# Ext_conn.net
KiCad netlist of a schematic drawn in Altium Designer
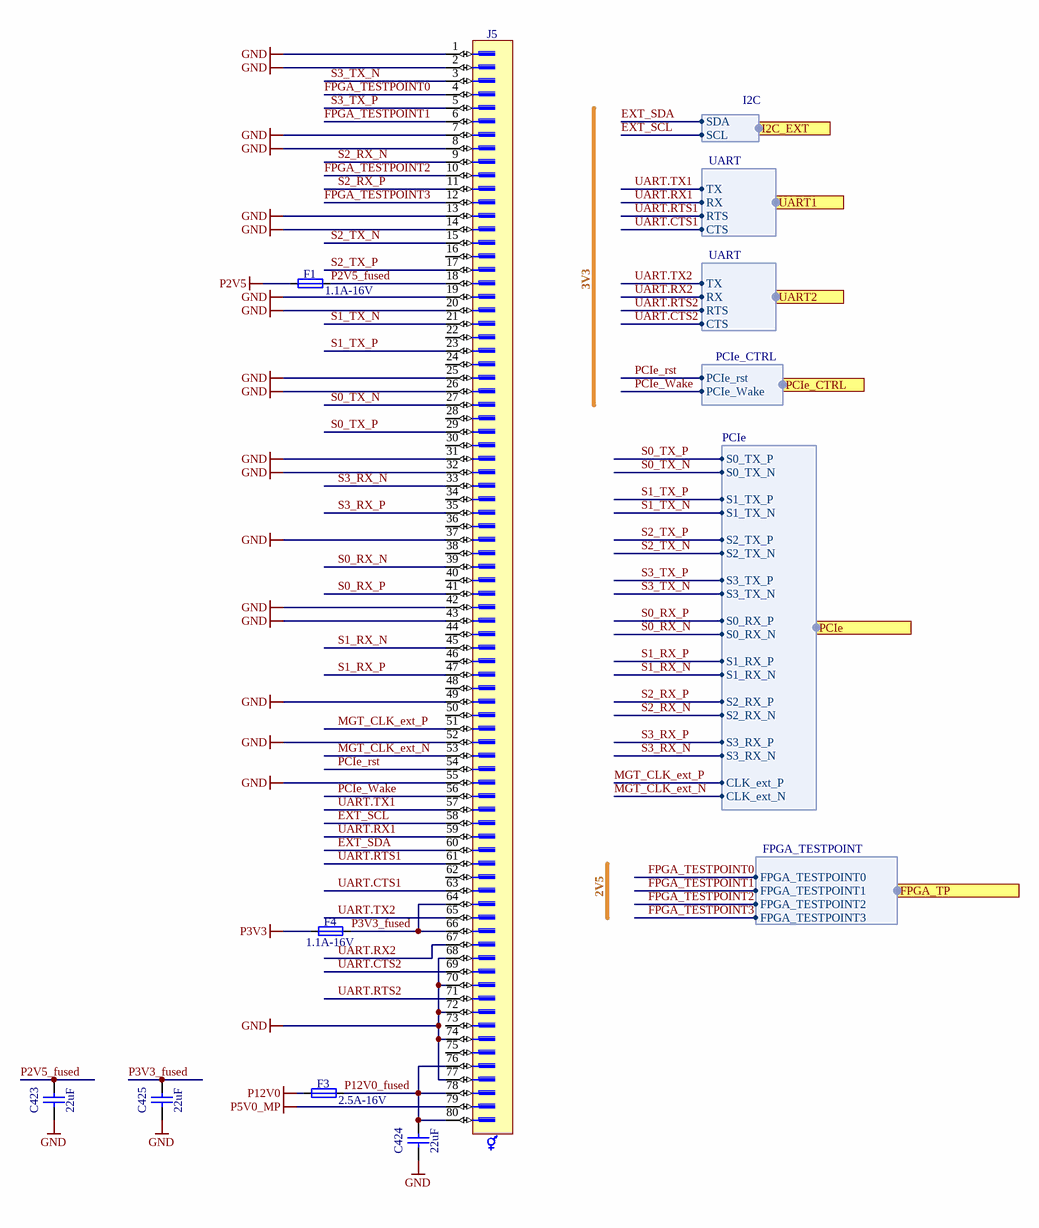
[diagram p0: Ext_conn.schdoc]

(export (version "E")
  (design (tool "Eeschema 10.0.6"))
  (components
    (comp (ref "C423")
      (value "22uF")
      (footprint "CAPC2012X135N")
      (description "Non-polarised capacitor")
      (fields
        (field (name "MANUFACTURER PART NUMBER") "CC0805_22UF_16V_10%_X5R")
        (field (name "MANUFACTURER") "GENERIC")
        (field (name "AUTHOR") "CERN DEM JLC")
      )
      (libsource (lib "Capacitors") (part "Capacitor - non polarized"))
    )
    (comp (ref "C424")
      (value "22uF")
      (footprint "CAPC2012X135N")
      (description "Non-polarised capacitor")
      (fields
        (field (name "MANUFACTURER PART NUMBER") "CC0805_22UF_16V_10%_X5R")
        (field (name "MANUFACTURER") "GENERIC")
        (field (name "AUTHOR") "CERN DEM JLC")
      )
      (libsource (lib "Capacitors") (part "Capacitor - non polarized"))
    )
    (comp (ref "C425")
      (value "22uF")
      (footprint "CAPC2012X135N")
      (description "Non-polarised capacitor")
      (fields
        (field (name "MANUFACTURER PART NUMBER") "CC0805_22UF_16V_10%_X5R")
        (field (name "MANUFACTURER") "GENERIC")
        (field (name "AUTHOR") "CERN DEM JLC")
      )
      (libsource (lib "Capacitors") (part "Capacitor - non polarized"))
    )
    (comp (ref "F1")
      (value "1.1A-16V")
      (footprint "FUSR_BOURNS_MF-MSMF_STYLE1(H85)")
      (description "Fuse")
      (fields
        (field (name "PART NUMBER") "FUSR_BOURNS_MF-MSMF110/16-2")
        (field (name "MANUFACTURER") "BOURNS")
        (field (name "AUTHOR") "CERN DEM JLC")
      )
      (libsource (lib "Eletro-mechanical") (part "Fuse"))
    )
    (comp (ref "F3")
      (value "2.5A-16V")
      (footprint "FUSR_BOURNS_MF-MSMF_STYLE2")
      (description "Fuse")
      (fields
        (field (name "PART NUMBER") "FUSR_BOURNS_MF-MSMF250/16X-2")
        (field (name "MANUFACTURER") "BOURNS")
        (field (name "AUTHOR") "CERN DEM JLC")
      )
      (libsource (lib "Eletro-mechanical") (part "Fuse"))
    )
    (comp (ref "F4")
      (value "1.1A-16V")
      (footprint "FUSR_BOURNS_MF-MSMF_STYLE1(H85)")
      (description "Fuse")
      (fields
        (field (name "PART NUMBER") "FUSR_BOURNS_MF-MSMF110/16-2")
        (field (name "MANUFACTURER") "BOURNS")
        (field (name "AUTHOR") "CERN DEM JLC")
      )
      (libsource (lib "Eletro-mechanical") (part "Fuse"))
    )
    (comp (ref "J5")
      (value "~")
      (footprint "SAMTEC_LSS-140-01-L-DV-A")
      (description "Connector 80 Hermaphroditic")
      (fields
        (field (name "PART NUMBER") "SAMTEC_LSS-140-01-L-DV-A")
        (field (name "MANUFACTURER") "SAMTEC")
        (field (name "AUTHOR") "CERN DEM JMW")
      )
      (libsource (lib "Connectors") (part "Connector 80 Hermaphroditic"))
    )
  )
  (nets
    (net (code "6") (name "/EXT_SCL") (class "Default")
      (node (ref "J5") (pin "58") (pinfunction "58_58") (pintype "bidirectional"))
    )
    (net (code "7") (name "/EXT_SDA") (class "Default")
      (node (ref "J5") (pin "60") (pinfunction "60_60") (pintype "bidirectional"))
    )
    (net (code "8") (name "/FPGA_TESTPOINT0") (class "Default")
      (node (ref "J5") (pin "4") (pinfunction "4_4") (pintype "bidirectional"))
    )
    (net (code "9") (name "/FPGA_TESTPOINT1") (class "Default")
      (node (ref "J5") (pin "6") (pinfunction "6_6") (pintype "bidirectional"))
    )
    (net (code "10") (name "/FPGA_TESTPOINT2") (class "Default")
      (node (ref "J5") (pin "10") (pinfunction "10_10") (pintype "bidirectional"))
    )
    (net (code "11") (name "/FPGA_TESTPOINT3") (class "Default")
      (node (ref "J5") (pin "12") (pinfunction "12_12") (pintype "bidirectional"))
    )
    (net (code "12") (name "/MGT_CLK_ext_N") (class "Default")
      (node (ref "J5") (pin "53") (pinfunction "53_53") (pintype "bidirectional"))
    )
    (net (code "13") (name "/MGT_CLK_ext_P") (class "Default")
      (node (ref "J5") (pin "51") (pinfunction "51_51") (pintype "bidirectional"))
    )
    (net (code "14") (name "/P2V5_fused") (class "Default")
      (node (ref "C423") (pin "2") (pinfunction "2_2") (pintype "passive"))
      (node (ref "F1") (pin "2") (pinfunction "2_2") (pintype "passive"))
      (node (ref "J5") (pin "18") (pinfunction "18_18") (pintype "bidirectional"))
    )
    (net (code "15") (name "/P3V3_fused") (class "Default")
      (node (ref "C425") (pin "2") (pinfunction "2_2") (pintype "passive"))
      (node (ref "F4") (pin "2") (pinfunction "2_2") (pintype "passive"))
      (node (ref "J5") (pin "64") (pinfunction "64_64") (pintype "bidirectional"))
      (node (ref "J5") (pin "66") (pinfunction "66_66") (pintype "bidirectional"))
    )
    (net (code "16") (name "/P12V0_fused") (class "Default")
      (node (ref "C424") (pin "2") (pinfunction "2_2") (pintype "passive"))
      (node (ref "F3") (pin "2") (pinfunction "2_2") (pintype "passive"))
      (node (ref "J5") (pin "76") (pinfunction "76_76") (pintype "bidirectional"))
      (node (ref "J5") (pin "78") (pinfunction "78_78") (pintype "bidirectional"))
      (node (ref "J5") (pin "80") (pinfunction "80_80") (pintype "bidirectional"))
    )
    (net (code "17") (name "/PCIe_Wake") (class "Default")
      (node (ref "J5") (pin "56") (pinfunction "56_56") (pintype "bidirectional"))
    )
    (net (code "18") (name "/PCIe_rst") (class "Default")
      (node (ref "J5") (pin "54") (pinfunction "54_54") (pintype "bidirectional"))
    )
    (net (code "19") (name "/S0_RX_N") (class "Default")
      (node (ref "J5") (pin "39") (pinfunction "39_39") (pintype "bidirectional"))
    )
    (net (code "20") (name "/S0_RX_P") (class "Default")
      (node (ref "J5") (pin "41") (pinfunction "41_41") (pintype "bidirectional"))
    )
    (net (code "21") (name "/S0_TX_N") (class "Default")
      (node (ref "J5") (pin "27") (pinfunction "27_27") (pintype "bidirectional"))
    )
    (net (code "22") (name "/S0_TX_P") (class "Default")
      (node (ref "J5") (pin "29") (pinfunction "29_29") (pintype "bidirectional"))
    )
    (net (code "23") (name "/S1_RX_N") (class "Default")
      (node (ref "J5") (pin "45") (pinfunction "45_45") (pintype "bidirectional"))
    )
    (net (code "24") (name "/S1_RX_P") (class "Default")
      (node (ref "J5") (pin "47") (pinfunction "47_47") (pintype "bidirectional"))
    )
    (net (code "25") (name "/S1_TX_N") (class "Default")
      (node (ref "J5") (pin "21") (pinfunction "21_21") (pintype "bidirectional"))
    )
    (net (code "26") (name "/S1_TX_P") (class "Default")
      (node (ref "J5") (pin "23") (pinfunction "23_23") (pintype "bidirectional"))
    )
    (net (code "27") (name "/S2_RX_N") (class "Default")
      (node (ref "J5") (pin "9") (pinfunction "9_9") (pintype "bidirectional"))
    )
    (net (code "28") (name "/S2_RX_P") (class "Default")
      (node (ref "J5") (pin "11") (pinfunction "11_11") (pintype "bidirectional"))
    )
    (net (code "29") (name "/S2_TX_N") (class "Default")
      (node (ref "J5") (pin "15") (pinfunction "15_15") (pintype "bidirectional"))
    )
    (net (code "30") (name "/S2_TX_P") (class "Default")
      (node (ref "J5") (pin "17") (pinfunction "17_17") (pintype "bidirectional"))
    )
    (net (code "31") (name "/S3_RX_N") (class "Default")
      (node (ref "J5") (pin "33") (pinfunction "33_33") (pintype "bidirectional"))
    )
    (net (code "32") (name "/S3_RX_P") (class "Default")
      (node (ref "J5") (pin "35") (pinfunction "35_35") (pintype "bidirectional"))
    )
    (net (code "33") (name "/S3_TX_N") (class "Default")
      (node (ref "J5") (pin "3") (pinfunction "3_3") (pintype "bidirectional"))
    )
    (net (code "34") (name "/S3_TX_P") (class "Default")
      (node (ref "J5") (pin "5") (pinfunction "5_5") (pintype "bidirectional"))
    )
    (net (code "35") (name "/UART.CTS1") (class "Default")
      (node (ref "J5") (pin "63") (pinfunction "63_63") (pintype "bidirectional"))
    )
    (net (code "36") (name "/UART.CTS2") (class "Default")
      (node (ref "J5") (pin "69") (pinfunction "69_69") (pintype "bidirectional"))
    )
    (net (code "37") (name "/UART.RTS1") (class "Default")
      (node (ref "J5") (pin "61") (pinfunction "61_61") (pintype "bidirectional"))
    )
    (net (code "38") (name "/UART.RTS2") (class "Default")
      (node (ref "J5") (pin "71") (pinfunction "71_71") (pintype "bidirectional"))
    )
    (net (code "39") (name "/UART.RX1") (class "Default")
      (node (ref "J5") (pin "59") (pinfunction "59_59") (pintype "bidirectional"))
    )
    (net (code "40") (name "/UART.RX2") (class "Default")
      (node (ref "J5") (pin "67") (pinfunction "67_67") (pintype "bidirectional"))
    )
    (net (code "41") (name "/UART.TX1") (class "Default")
      (node (ref "J5") (pin "57") (pinfunction "57_57") (pintype "bidirectional"))
    )
    (net (code "42") (name "/UART.TX2") (class "Default")
      (node (ref "J5") (pin "65") (pinfunction "65_65") (pintype "bidirectional"))
    )
    (net (code "48") (name "GND") (class "Default")
      (node (ref "C423") (pin "1") (pinfunction "1_1") (pintype "passive"))
      (node (ref "C424") (pin "1") (pinfunction "1_1") (pintype "passive"))
      (node (ref "C425") (pin "1") (pinfunction "1_1") (pintype "passive"))
      (node (ref "J5") (pin "1") (pinfunction "1_1") (pintype "bidirectional"))
      (node (ref "J5") (pin "13") (pinfunction "13_13") (pintype "bidirectional"))
      (node (ref "J5") (pin "14") (pinfunction "14_14") (pintype "bidirectional"))
      (node (ref "J5") (pin "19") (pinfunction "19_19") (pintype "bidirectional"))
      (node (ref "J5") (pin "2") (pinfunction "2_2") (pintype "bidirectional"))
      (node (ref "J5") (pin "20") (pinfunction "20_20") (pintype "bidirectional"))
      (node (ref "J5") (pin "25") (pinfunction "25_25") (pintype "bidirectional"))
      (node (ref "J5") (pin "26") (pinfunction "26_26") (pintype "bidirectional"))
      (node (ref "J5") (pin "31") (pinfunction "31_31") (pintype "bidirectional"))
      (node (ref "J5") (pin "32") (pinfunction "32_32") (pintype "bidirectional"))
      (node (ref "J5") (pin "37") (pinfunction "37_37") (pintype "bidirectional"))
      (node (ref "J5") (pin "42") (pinfunction "42_42") (pintype "bidirectional"))
      (node (ref "J5") (pin "43") (pinfunction "43_43") (pintype "bidirectional"))
      (node (ref "J5") (pin "49") (pinfunction "49_49") (pintype "bidirectional"))
      (node (ref "J5") (pin "52") (pinfunction "52_52") (pintype "bidirectional"))
      (node (ref "J5") (pin "55") (pinfunction "55_55") (pintype "bidirectional"))
      (node (ref "J5") (pin "68") (pinfunction "68_68") (pintype "bidirectional"))
      (node (ref "J5") (pin "7") (pinfunction "7_7") (pintype "bidirectional"))
      (node (ref "J5") (pin "70") (pinfunction "70_70") (pintype "bidirectional"))
      (node (ref "J5") (pin "72") (pinfunction "72_72") (pintype "bidirectional"))
      (node (ref "J5") (pin "74") (pinfunction "74_74") (pintype "bidirectional"))
      (node (ref "J5") (pin "77") (pinfunction "77_77") (pintype "bidirectional"))
      (node (ref "J5") (pin "8") (pinfunction "8_8") (pintype "bidirectional"))
    )
    (net (code "49") (name "P2V5") (class "Default")
      (node (ref "F1") (pin "1") (pinfunction "1_1") (pintype "passive"))
    )
    (net (code "50") (name "P3V3") (class "Default")
      (node (ref "F4") (pin "1") (pinfunction "1_1") (pintype "passive"))
    )
    (net (code "51") (name "P5V0_MP") (class "Default")
      (node (ref "J5") (pin "79") (pinfunction "79_79") (pintype "bidirectional"))
    )
    (net (code "52") (name "P12V0") (class "Default")
      (node (ref "F3") (pin "1") (pinfunction "1_1") (pintype "passive"))
    )
    (net (code "53") (name "unconnected-(J5-Pad16)") (class "Default")
      (node (ref "J5") (pin "16") (pinfunction "16_16") (pintype "bidirectional"))
    )
    (net (code "54") (name "unconnected-(J5-Pad22)") (class "Default")
      (node (ref "J5") (pin "22") (pinfunction "22_22") (pintype "bidirectional"))
    )
    (net (code "55") (name "unconnected-(J5-Pad24)") (class "Default")
      (node (ref "J5") (pin "24") (pinfunction "24_24") (pintype "bidirectional"))
    )
    (net (code "56") (name "unconnected-(J5-Pad28)") (class "Default")
      (node (ref "J5") (pin "28") (pinfunction "28_28") (pintype "bidirectional"))
    )
    (net (code "57") (name "unconnected-(J5-Pad30)") (class "Default")
      (node (ref "J5") (pin "30") (pinfunction "30_30") (pintype "bidirectional"))
    )
    (net (code "58") (name "unconnected-(J5-Pad34)") (class "Default")
      (node (ref "J5") (pin "34") (pinfunction "34_34") (pintype "bidirectional"))
    )
    (net (code "59") (name "unconnected-(J5-Pad36)") (class "Default")
      (node (ref "J5") (pin "36") (pinfunction "36_36") (pintype "bidirectional"))
    )
    (net (code "60") (name "unconnected-(J5-Pad38)") (class "Default")
      (node (ref "J5") (pin "38") (pinfunction "38_38") (pintype "bidirectional"))
    )
    (net (code "61") (name "unconnected-(J5-Pad40)") (class "Default")
      (node (ref "J5") (pin "40") (pinfunction "40_40") (pintype "bidirectional"))
    )
    (net (code "62") (name "unconnected-(J5-Pad44)") (class "Default")
      (node (ref "J5") (pin "44") (pinfunction "44_44") (pintype "bidirectional"))
    )
    (net (code "63") (name "unconnected-(J5-Pad46)") (class "Default")
      (node (ref "J5") (pin "46") (pinfunction "46_46") (pintype "bidirectional"))
    )
    (net (code "64") (name "unconnected-(J5-Pad48)") (class "Default")
      (node (ref "J5") (pin "48") (pinfunction "48_48") (pintype "bidirectional"))
    )
    (net (code "65") (name "unconnected-(J5-Pad50)") (class "Default")
      (node (ref "J5") (pin "50") (pinfunction "50_50") (pintype "bidirectional"))
    )
    (net (code "66") (name "unconnected-(J5-Pad62)") (class "Default")
      (node (ref "J5") (pin "62") (pinfunction "62_62") (pintype "bidirectional"))
    )
    (net (code "67") (name "unconnected-(J5-Pad73)") (class "Default")
      (node (ref "J5") (pin "73") (pinfunction "73_73") (pintype "bidirectional"))
    )
    (net (code "68") (name "unconnected-(J5-Pad75)") (class "Default")
      (node (ref "J5") (pin "75") (pinfunction "75_75") (pintype "bidirectional"))
    )
  )
)
